# mainBoardV2.net
KiCad netlist of a schematic drawn in EAGLE
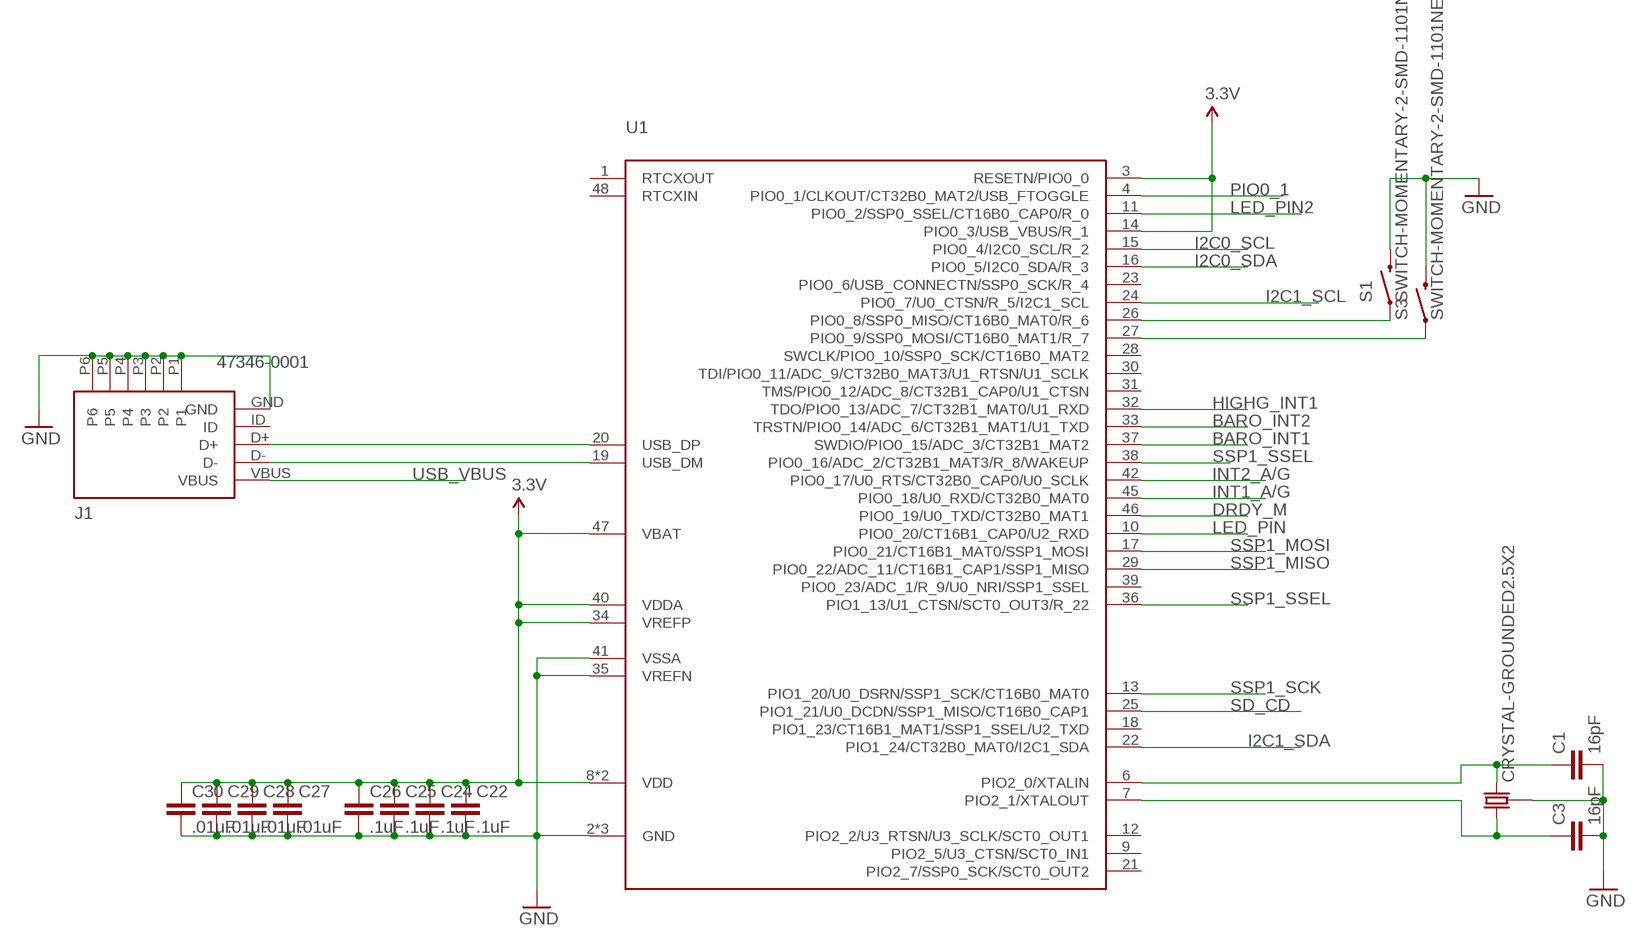
[diagram p0: schematic, sheet 1]
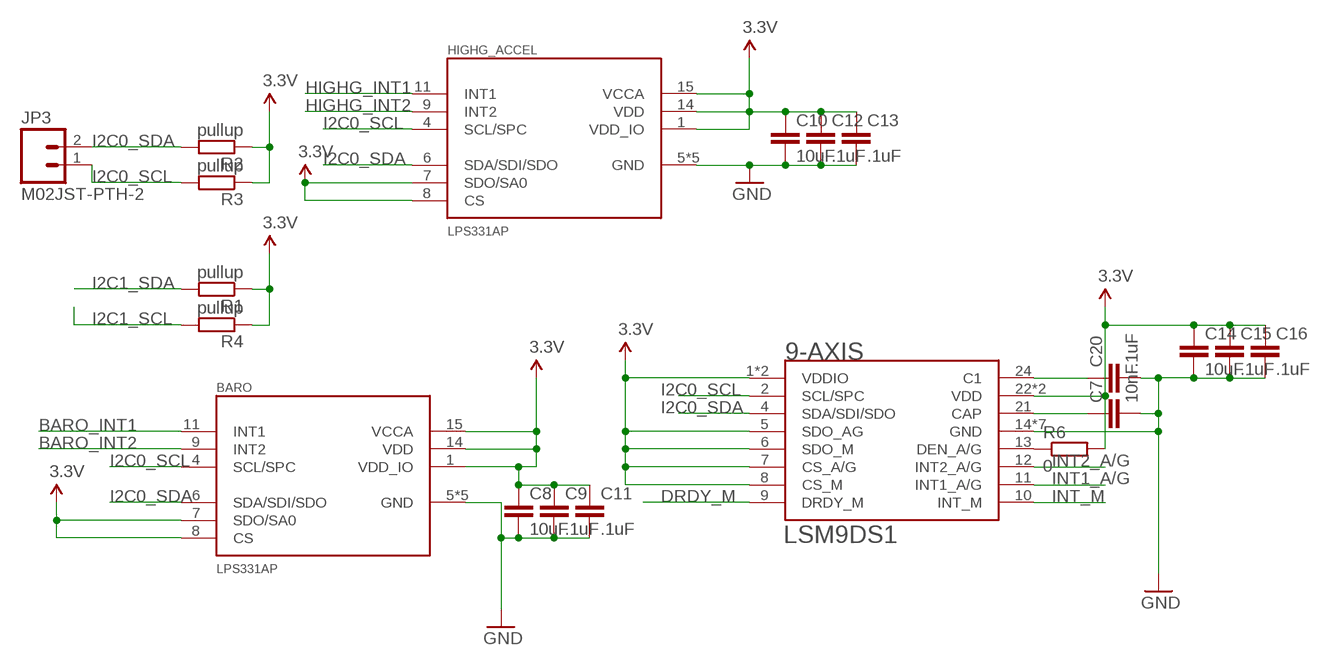
[diagram p1: schematic, sheet 2]
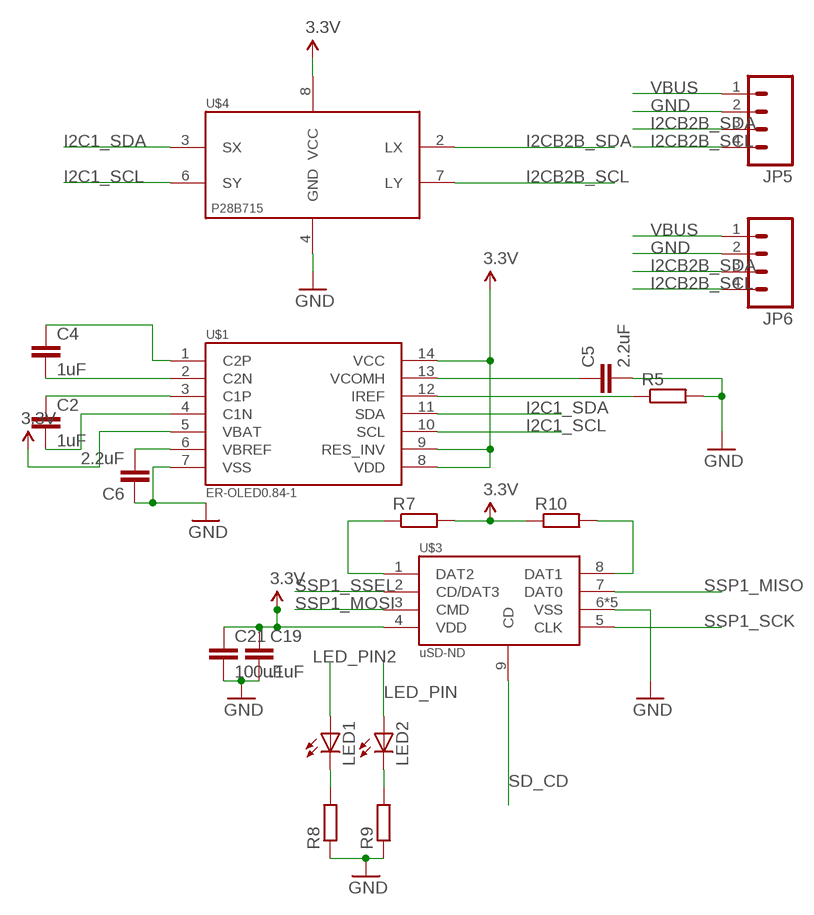
[diagram p2: schematic, sheet 3]
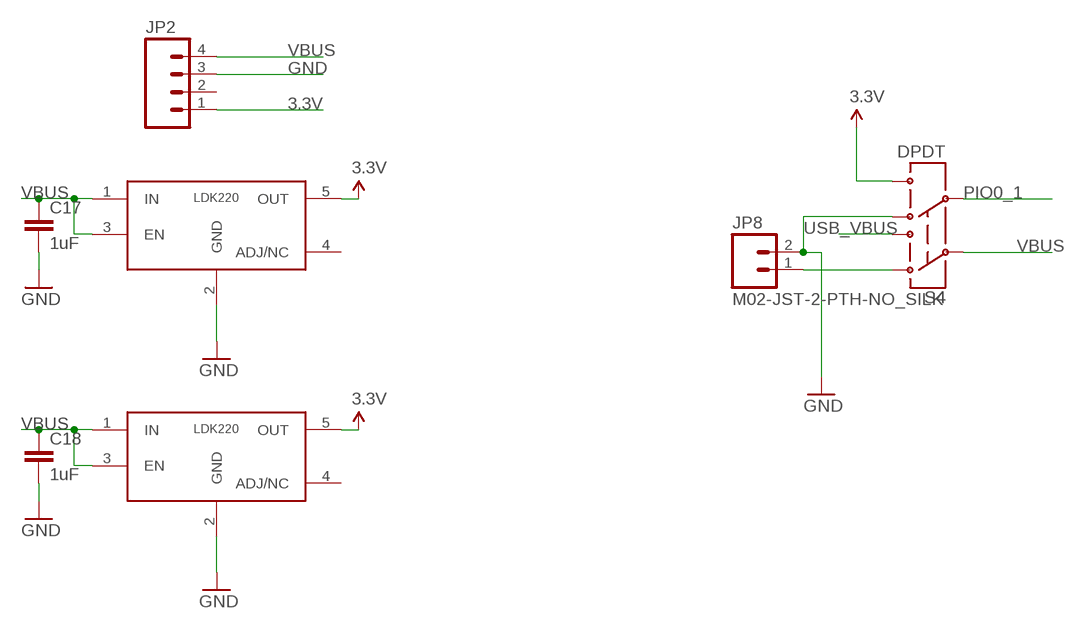
[diagram p3: schematic, sheet 4]

(export (version "E")
  (design (tool "Eeschema 10.0.6"))
  (components
    (comp (ref "C2")
      (value "1uF")
      (footprint "eagle-import:C0402")
      (fields (field (name "MPN") "MC0402X105M6R3CT"))
      (libsource (lib "eagle-import") (part "C0402"))
    )
    (comp (ref "C4")
      (value "1uF")
      (footprint "eagle-import:C0402")
      (fields (field (name "MPN") "MC0402X105M6R3CT"))
      (libsource (lib "eagle-import") (part "C0402"))
    )
    (comp (ref "C5")
      (value "2.2uF")
      (footprint "eagle-import:C0402")
      (fields (field (name "MPN") "C1005X6S0G225M050BC"))
      (libsource (lib "eagle-import") (part "C0402"))
    )
    (comp (ref "C6")
      (value "2.2uF")
      (footprint "eagle-import:C0402")
      (fields (field (name "MPN") "C1005X6S0G225M050BC"))
      (libsource (lib "eagle-import") (part "C0402"))
    )
    (comp (ref "C19")
      (value ".1uF")
      (footprint "eagle-import:C0402")
      (libsource (lib "eagle-import") (part "C0402"))
    )
    (comp (ref "C21")
      (value "100uF")
      (footprint "eagle-import:C1206")
      (libsource (lib "eagle-import") (part "CC1206"))
    )
    (comp (ref "JP5")
      (value "M04JST")
      (footprint "eagle-import:1X04-1.5MM_JST")
      (libsource (lib "eagle-import") (part "M04JST"))
    )
    (comp (ref "JP6")
      (value "M04JST")
      (footprint "eagle-import:1X04-1.5MM_JST")
      (libsource (lib "eagle-import") (part "M04JST"))
    )
    (comp (ref "LED1")
      (value "LEDCHIPLED_0603")
      (footprint "eagle-import:CHIPLED_0603")
      (libsource (lib "eagle-import") (part "LEDCHIPLED_0603"))
    )
    (comp (ref "LED2")
      (value "LEDCHIPLED_0603")
      (footprint "eagle-import:CHIPLED_0603")
      (libsource (lib "eagle-import") (part "LEDCHIPLED_0603"))
    )
    (comp (ref "R5")
      (value "R0402")
      (footprint "eagle-import:R0402")
      (libsource (lib "eagle-import") (part "R0402"))
    )
    (comp (ref "R7")
      (value "R0402")
      (footprint "eagle-import:R0402")
      (libsource (lib "eagle-import") (part "R0402"))
    )
    (comp (ref "R8")
      (value "R0402")
      (footprint "eagle-import:R0402")
      (libsource (lib "eagle-import") (part "R0402"))
    )
    (comp (ref "R9")
      (value "R0402")
      (footprint "eagle-import:R0402")
      (libsource (lib "eagle-import") (part "R0402"))
    )
    (comp (ref "R10")
      (value "R0402")
      (footprint "eagle-import:R0402")
      (libsource (lib "eagle-import") (part "R0402"))
    )
    (comp (ref "U$1")
      (value "ER-OLED0.84-1")
      (footprint "eagle-import:MOLEX_52892-1433")
      (libsource (lib "eagle-import") (part "ER-OLED0.84-1"))
    )
    (comp (ref "U$3")
      (value "MICROSD-CD")
      (footprint "eagle-import:MOLEX_SD-47352-101")
      (libsource (lib "eagle-import") (part "MICROSD-CD"))
    )
    (comp (ref "U$4")
      (value "P82B715")
      (footprint "eagle-import:SO8")
      (libsource (lib "eagle-import") (part "P82B715"))
    )
    (comp (ref "9-AXIS")
      (value "LSM9DS1")
      (footprint "eagle-import:LGA-24L-3.5X3X1")
      (libsource (lib "eagle-import") (part "LSM9DS1"))
    )
    (comp (ref "BARO")
      (value "LPS331AP")
      (footprint "eagle-import:LGA-16-3X3X1")
      (fields (field (name "MPN") "LPS331APTR"))
      (libsource (lib "eagle-import") (part "LPS331AP"))
    )
    (comp (ref "C7")
      (value "10nF")
      (footprint "eagle-import:C0402")
      (fields (field (name "MPN") "S103M47Z5UN63L0R"))
      (libsource (lib "eagle-import") (part "C0402"))
    )
    (comp (ref "C8")
      (value "10uF")
      (footprint "eagle-import:C0402")
      (libsource (lib "eagle-import") (part "C0402"))
    )
    (comp (ref "C9")
      (value ".1uF")
      (footprint "eagle-import:C0402")
      (libsource (lib "eagle-import") (part "C0402"))
    )
    (comp (ref "C10")
      (value "10uF")
      (footprint "eagle-import:C0402")
      (libsource (lib "eagle-import") (part "C0402"))
    )
    (comp (ref "C11")
      (value ".1uF")
      (footprint "eagle-import:C0402")
      (libsource (lib "eagle-import") (part "C0402"))
    )
    (comp (ref "C12")
      (value ".1uF")
      (footprint "eagle-import:C0402")
      (libsource (lib "eagle-import") (part "C0402"))
    )
    (comp (ref "C13")
      (value ".1uF")
      (footprint "eagle-import:C0402")
      (libsource (lib "eagle-import") (part "C0402"))
    )
    (comp (ref "C14")
      (value "10uF")
      (footprint "eagle-import:C0402")
      (libsource (lib "eagle-import") (part "C0402"))
    )
    (comp (ref "C15")
      (value ".1uF")
      (footprint "eagle-import:C0402")
      (libsource (lib "eagle-import") (part "C0402"))
    )
    (comp (ref "C16")
      (value ".1uF")
      (footprint "eagle-import:C0402")
      (libsource (lib "eagle-import") (part "C0402"))
    )
    (comp (ref "C20")
      (value ".1uF")
      (footprint "eagle-import:C0402")
      (fields (field (name "MPN") "S103M47Z5UN63L0R"))
      (libsource (lib "eagle-import") (part "C0402"))
    )
    (comp (ref "HIGHG_ACCEL")
      (value "LPS331AP")
      (footprint "eagle-import:LGA-16-3X3X1")
      (fields (field (name "MPN") "LPS331APTR"))
      (libsource (lib "eagle-import") (part "LPS331AP"))
    )
    (comp (ref "JP3")
      (value "M02JST-PTH-2")
      (footprint "eagle-import:JST-2-PTH")
      (libsource (lib "eagle-import") (part "M02JST-PTH-2"))
    )
    (comp (ref "R1")
      (value "pullup")
      (footprint "eagle-import:R0805")
      (libsource (lib "eagle-import") (part "R0805"))
    )
    (comp (ref "R2")
      (value "pullup")
      (footprint "eagle-import:R0402")
      (libsource (lib "eagle-import") (part "R0402"))
    )
    (comp (ref "R3")
      (value "pullup")
      (footprint "eagle-import:R0402")
      (libsource (lib "eagle-import") (part "R0402"))
    )
    (comp (ref "R4")
      (value "pullup")
      (footprint "eagle-import:R0805")
      (libsource (lib "eagle-import") (part "R0805"))
    )
    (comp (ref "R6")
      (value "0")
      (footprint "eagle-import:R0402")
      (libsource (lib "eagle-import") (part "R0402"))
    )
    (comp (ref "C17")
      (value "1uF")
      (footprint "eagle-import:C0402")
      (libsource (lib "eagle-import") (part "C0402"))
    )
    (comp (ref "C18")
      (value "1uF")
      (footprint "eagle-import:C0402")
      (libsource (lib "eagle-import") (part "C0402"))
    )
    (comp (ref "JP2")
      (value "M04JST")
      (footprint "eagle-import:1X04-1.5MM_JST")
      (libsource (lib "eagle-import") (part "M04JST"))
    )
    (comp (ref "JP8")
      (value "M02-JST-2-PTH-NO_SILK")
      (footprint "eagle-import:JST-2-PTH-NS")
      (libsource (lib "eagle-import") (part "M02-JST-2-PTH-NO_SILK"))
    )
    (comp (ref "S4")
      (value "DPDT")
      (footprint "eagle-import:AYZ0202")
      (libsource (lib "eagle-import") (part "SWITCH-DPDTAYZ0202"))
    )
    (comp (ref "U$2")
      (value "LDK220M33R")
      (footprint "eagle-import:SOT23-5")
      (libsource (lib "eagle-import") (part "LDK220M33R"))
    )
    (comp (ref "U$6")
      (value "LDK220M33R")
      (footprint "eagle-import:SOT23-5")
      (libsource (lib "eagle-import") (part "LDK220M33R"))
    )
    (comp (ref "C1")
      (value "16pF")
      (footprint "eagle-import:C0402")
      (libsource (lib "eagle-import") (part "C0402"))
    )
    (comp (ref "C3")
      (value "16pF")
      (footprint "eagle-import:C0402")
      (libsource (lib "eagle-import") (part "C0402"))
    )
    (comp (ref "C22")
      (value ".1uF")
      (footprint "eagle-import:C0402")
      (libsource (lib "eagle-import") (part "C0402"))
    )
    (comp (ref "C24")
      (value ".1uF")
      (footprint "eagle-import:C0402")
      (libsource (lib "eagle-import") (part "C0402"))
    )
    (comp (ref "C25")
      (value ".1uF")
      (footprint "eagle-import:C0402")
      (libsource (lib "eagle-import") (part "C0402"))
    )
    (comp (ref "C26")
      (value ".1uF")
      (footprint "eagle-import:C0402")
      (libsource (lib "eagle-import") (part "C0402"))
    )
    (comp (ref "C27")
      (value ".01uF")
      (footprint "eagle-import:C0402")
      (libsource (lib "eagle-import") (part "C0402"))
    )
    (comp (ref "C28")
      (value ".01uF")
      (footprint "eagle-import:C0402")
      (libsource (lib "eagle-import") (part "C0402"))
    )
    (comp (ref "C29")
      (value ".01uF")
      (footprint "eagle-import:C0402")
      (libsource (lib "eagle-import") (part "C0402"))
    )
    (comp (ref "C30")
      (value ".01uF")
      (footprint "eagle-import:C0402")
      (libsource (lib "eagle-import") (part "C0402"))
    )
    (comp (ref "J1")
      (value "47346-0001")
      (footprint "eagle-import:MICRO_USB")
      (fields (field (name "PARTNO") "AS-ITM-00021"))
      (libsource (lib "eagle-import") (part "MICRO-USB"))
    )
    (comp (ref "S1")
      (value "SWITCH-MOMENTARY-2-SMD-1101NE")
      (footprint "eagle-import:TACTILE-SWITCH-1101NE")
      (libsource (lib "eagle-import") (part "SWITCH-MOMENTARY-2-SMD-1101NE"))
    )
    (comp (ref "S3")
      (value "SWITCH-MOMENTARY-2-SMD-1101NE")
      (footprint "eagle-import:TACTILE-SWITCH-1101NE")
      (libsource (lib "eagle-import") (part "SWITCH-MOMENTARY-2-SMD-1101NE"))
    )
    (comp (ref "U$5")
      (value "CRYSTAL-GROUNDED2.5X2")
      (footprint "eagle-import:CRYSTAL-SMD-2.5X2")
      (libsource (lib "eagle-import") (part "CRYSTAL-GROUNDED2.5X2"))
    )
    (comp (ref "U1")
      (value "LPC11U68JBD48")
      (footprint "eagle-import:LQFP48")
      (libsource (lib "eagle-import") (part "LPC11U68JBD48"))
    )
  )
  (nets
    (net (code "1") (name "3.3V") (class "Default")
      (node (ref "9-AXIS") (pin "1") (pinfunction "VDDIO_1") (pintype "bidirectional"))
      (node (ref "9-AXIS") (pin "22") (pinfunction "VDD_22") (pintype "bidirectional"))
      (node (ref "9-AXIS") (pin "23") (pinfunction "VDD_23") (pintype "bidirectional"))
      (node (ref "9-AXIS") (pin "3") (pinfunction "VDDIO_3") (pintype "bidirectional"))
      (node (ref "9-AXIS") (pin "5") (pinfunction "SDO_AG_5") (pintype "bidirectional"))
      (node (ref "9-AXIS") (pin "6") (pinfunction "SDO_M_6") (pintype "bidirectional"))
      (node (ref "9-AXIS") (pin "7") (pinfunction "CS_A/G_7") (pintype "bidirectional"))
      (node (ref "9-AXIS") (pin "8") (pinfunction "CS_M_8") (pintype "bidirectional"))
      (node (ref "BARO") (pin "1") (pinfunction "VDD_IO_1") (pintype "bidirectional"))
      (node (ref "BARO") (pin "14") (pinfunction "VDD_14") (pintype "bidirectional"))
      (node (ref "BARO") (pin "15") (pinfunction "VCCA_15") (pintype "bidirectional"))
      (node (ref "BARO") (pin "7") (pinfunction "SDO/SA0_7") (pintype "bidirectional"))
      (node (ref "BARO") (pin "8") (pinfunction "CS_8") (pintype "bidirectional"))
      (node (ref "C10") (pin "1") (pinfunction "1_1") (pintype "passive"))
      (node (ref "C11") (pin "1") (pinfunction "1_1") (pintype "passive"))
      (node (ref "C12") (pin "1") (pinfunction "1_1") (pintype "passive"))
      (node (ref "C13") (pin "1") (pinfunction "1_1") (pintype "passive"))
      (node (ref "C14") (pin "1") (pinfunction "1_1") (pintype "passive"))
      (node (ref "C15") (pin "1") (pinfunction "1_1") (pintype "passive"))
      (node (ref "C16") (pin "1") (pinfunction "1_1") (pintype "passive"))
      (node (ref "C19") (pin "1") (pinfunction "1_1") (pintype "passive"))
      (node (ref "C21") (pin "1") (pinfunction "1_1") (pintype "passive"))
      (node (ref "C22") (pin "1") (pinfunction "1_1") (pintype "passive"))
      (node (ref "C24") (pin "1") (pinfunction "1_1") (pintype "passive"))
      (node (ref "C25") (pin "1") (pinfunction "1_1") (pintype "passive"))
      (node (ref "C26") (pin "1") (pinfunction "1_1") (pintype "passive"))
      (node (ref "C27") (pin "1") (pinfunction "1_1") (pintype "passive"))
      (node (ref "C28") (pin "1") (pinfunction "1_1") (pintype "passive"))
      (node (ref "C29") (pin "1") (pinfunction "1_1") (pintype "passive"))
      (node (ref "C30") (pin "1") (pinfunction "1_1") (pintype "passive"))
      (node (ref "C8") (pin "1") (pinfunction "1_1") (pintype "passive"))
      (node (ref "C9") (pin "1") (pinfunction "1_1") (pintype "passive"))
      (node (ref "HIGHG_ACCEL") (pin "1") (pinfunction "VDD_IO_1") (pintype "bidirectional"))
      (node (ref "HIGHG_ACCEL") (pin "14") (pinfunction "VDD_14") (pintype "bidirectional"))
      (node (ref "HIGHG_ACCEL") (pin "15") (pinfunction "VCCA_15") (pintype "bidirectional"))
      (node (ref "HIGHG_ACCEL") (pin "7") (pinfunction "SDO/SA0_7") (pintype "bidirectional"))
      (node (ref "HIGHG_ACCEL") (pin "8") (pinfunction "CS_8") (pintype "bidirectional"))
      (node (ref "JP2") (pin "1") (pinfunction "1_1") (pintype "passive"))
      (node (ref "R1") (pin "1") (pinfunction "1_1") (pintype "passive"))
      (node (ref "R10") (pin "1") (pinfunction "1_1") (pintype "passive"))
      (node (ref "R2") (pin "1") (pinfunction "1_1") (pintype "passive"))
      (node (ref "R3") (pin "1") (pinfunction "1_1") (pintype "passive"))
      (node (ref "R4") (pin "1") (pinfunction "1_1") (pintype "passive"))
      (node (ref "R6") (pin "2") (pinfunction "2_2") (pintype "passive"))
      (node (ref "R7") (pin "2") (pinfunction "2_2") (pintype "passive"))
      (node (ref "S4") (pin "6") (pinfunction "6_6") (pintype "bidirectional"))
      (node (ref "U$1") (pin "14") (pinfunction "VCC_14") (pintype "bidirectional"))
      (node (ref "U$1") (pin "5") (pinfunction "VBAT_5") (pintype "bidirectional"))
      (node (ref "U$1") (pin "8") (pinfunction "VDD_8") (pintype "bidirectional"))
      (node (ref "U$1") (pin "9") (pinfunction "RES_INV_9") (pintype "bidirectional"))
      (node (ref "U$2") (pin "5") (pinfunction "OUT_5") (pintype "bidirectional"))
      (node (ref "U$3") (pin "4") (pinfunction "VDD_4") (pintype "bidirectional"))
      (node (ref "U$4") (pin "8") (pinfunction "VCC_8") (pintype "bidirectional"))
      (node (ref "U$6") (pin "5") (pinfunction "OUT_5") (pintype "bidirectional"))
      (node (ref "U1") (pin "14") (pinfunction "PIO0_3/USB_VBUS/R_1_14") (pintype "bidirectional"))
      (node (ref "U1") (pin "3") (pinfunction "RESETN/PIO0_0_3") (pintype "bidirectional"))
      (node (ref "U1") (pin "34") (pinfunction "VREFP_34") (pintype "bidirectional"))
      (node (ref "U1") (pin "40") (pinfunction "VDDA_40") (pintype "bidirectional"))
      (node (ref "U1") (pin "44") (pinfunction "VDD_44") (pintype "bidirectional"))
      (node (ref "U1") (pin "47") (pinfunction "VBAT_47") (pintype "bidirectional"))
      (node (ref "U1") (pin "8") (pinfunction "VDD_8") (pintype "bidirectional"))
    )
    (net (code "2") (name "BARO_INT1") (class "Default")
      (node (ref "BARO") (pin "11") (pinfunction "INT1_11") (pintype "bidirectional"))
      (node (ref "U1") (pin "37") (pinfunction "SWDIO/PIO0_15/ADC_3/CT32B1_MAT2_37") (pintype "bidirectional"))
    )
    (net (code "3") (name "BARO_INT2") (class "Default")
      (node (ref "BARO") (pin "9") (pinfunction "INT2_9") (pintype "bidirectional"))
      (node (ref "U1") (pin "33") (pinfunction "TRSTN/PIO0_14/ADC_6/CT32B1_MAT1/U1_TXD_33") (pintype "bidirectional"))
    )
    (net (code "4") (name "DRDY_M") (class "Default")
      (node (ref "9-AXIS") (pin "9") (pinfunction "DRDY_M_9") (pintype "bidirectional"))
      (node (ref "U1") (pin "46") (pinfunction "PIO0_19/U0_TXD/CT32B0_MAT1_46") (pintype "bidirectional"))
    )
    (net (code "5") (name "GND") (class "Default")
      (node (ref "9-AXIS") (pin "14") (pinfunction "GND_14") (pintype "bidirectional"))
      (node (ref "9-AXIS") (pin "15") (pinfunction "GND_15") (pintype "bidirectional"))
      (node (ref "9-AXIS") (pin "16") (pinfunction "GND_16") (pintype "bidirectional"))
      (node (ref "9-AXIS") (pin "17") (pinfunction "GND_17") (pintype "bidirectional"))
      (node (ref "9-AXIS") (pin "18") (pinfunction "GND_18") (pintype "bidirectional"))
      (node (ref "9-AXIS") (pin "19") (pinfunction "GND_19") (pintype "bidirectional"))
      (node (ref "9-AXIS") (pin "20") (pinfunction "GND_20") (pintype "bidirectional"))
      (node (ref "BARO") (pin "10") (pinfunction "GND_10") (pintype "bidirectional"))
      (node (ref "BARO") (pin "12") (pinfunction "GND_12") (pintype "bidirectional"))
      (node (ref "BARO") (pin "13") (pinfunction "GND_13") (pintype "bidirectional"))
      (node (ref "BARO") (pin "16") (pinfunction "GND_16") (pintype "bidirectional"))
      (node (ref "BARO") (pin "5") (pinfunction "GND_5") (pintype "bidirectional"))
      (node (ref "C1") (pin "2") (pinfunction "2_2") (pintype "passive"))
      (node (ref "C10") (pin "2") (pinfunction "2_2") (pintype "passive"))
      (node (ref "C11") (pin "2") (pinfunction "2_2") (pintype "passive"))
      (node (ref "C12") (pin "2") (pinfunction "2_2") (pintype "passive"))
      (node (ref "C13") (pin "2") (pinfunction "2_2") (pintype "passive"))
      (node (ref "C14") (pin "2") (pinfunction "2_2") (pintype "passive"))
      (node (ref "C15") (pin "2") (pinfunction "2_2") (pintype "passive"))
      (node (ref "C16") (pin "2") (pinfunction "2_2") (pintype "passive"))
      (node (ref "C17") (pin "2") (pinfunction "2_2") (pintype "passive"))
      (node (ref "C18") (pin "2") (pinfunction "2_2") (pintype "passive"))
      (node (ref "C19") (pin "2") (pinfunction "2_2") (pintype "passive"))
      (node (ref "C20") (pin "2") (pinfunction "2_2") (pintype "passive"))
      (node (ref "C21") (pin "2") (pinfunction "2_2") (pintype "passive"))
      (node (ref "C22") (pin "2") (pinfunction "2_2") (pintype "passive"))
      (node (ref "C24") (pin "2") (pinfunction "2_2") (pintype "passive"))
      (node (ref "C25") (pin "2") (pinfunction "2_2") (pintype "passive"))
      (node (ref "C26") (pin "2") (pinfunction "2_2") (pintype "passive"))
      (node (ref "C27") (pin "2") (pinfunction "2_2") (pintype "passive"))
      (node (ref "C28") (pin "2") (pinfunction "2_2") (pintype "passive"))
      (node (ref "C29") (pin "2") (pinfunction "2_2") (pintype "passive"))
      (node (ref "C3") (pin "2") (pinfunction "2_2") (pintype "passive"))
      (node (ref "C30") (pin "2") (pinfunction "2_2") (pintype "passive"))
      (node (ref "C5") (pin "2") (pinfunction "2_2") (pintype "passive"))
      (node (ref "C6") (pin "1") (pinfunction "1_1") (pintype "passive"))
      (node (ref "C7") (pin "2") (pinfunction "2_2") (pintype "passive"))
      (node (ref "C8") (pin "2") (pinfunction "2_2") (pintype "passive"))
      (node (ref "C9") (pin "2") (pinfunction "2_2") (pintype "passive"))
      (node (ref "HIGHG_ACCEL") (pin "10") (pinfunction "GND_10") (pintype "bidirectional"))
      (node (ref "HIGHG_ACCEL") (pin "12") (pinfunction "GND_12") (pintype "bidirectional"))
      (node (ref "HIGHG_ACCEL") (pin "13") (pinfunction "GND_13") (pintype "bidirectional"))
      (node (ref "HIGHG_ACCEL") (pin "16") (pinfunction "GND_16") (pintype "bidirectional"))
      (node (ref "HIGHG_ACCEL") (pin "5") (pinfunction "GND_5") (pintype "bidirectional"))
      (node (ref "J1") (pin "GND") (pinfunction "GND_GND") (pintype "bidirectional"))
      (node (ref "J1") (pin "P1") (pinfunction "P1_P1") (pintype "bidirectional"))
      (node (ref "J1") (pin "P2") (pinfunction "P2_P2") (pintype "bidirectional"))
      (node (ref "J1") (pin "P3") (pinfunction "P3_P3") (pintype "bidirectional"))
      (node (ref "J1") (pin "P4") (pinfunction "P4_P4") (pintype "bidirectional"))
      (node (ref "J1") (pin "P5") (pinfunction "P5_P5") (pintype "bidirectional"))
      (node (ref "J1") (pin "P6") (pinfunction "P6_P6") (pintype "bidirectional"))
      (node (ref "JP2") (pin "3") (pinfunction "3_3") (pintype "passive"))
      (node (ref "JP5") (pin "2") (pinfunction "2_2") (pintype "passive"))
      (node (ref "JP6") (pin "2") (pinfunction "2_2") (pintype "passive"))
      (node (ref "JP8") (pin "2") (pinfunction "2_2") (pintype "passive"))
      (node (ref "R5") (pin "2") (pinfunction "2_2") (pintype "passive"))
      (node (ref "R8") (pin "1") (pinfunction "1_1") (pintype "passive"))
      (node (ref "R9") (pin "1") (pinfunction "1_1") (pintype "passive"))
      (node (ref "S1") (pin "2") (pinfunction "2_2") (pintype "passive"))
      (node (ref "S3") (pin "2") (pinfunction "2_2") (pintype "passive"))
      (node (ref "S4") (pin "4") (pinfunction "4_4") (pintype "bidirectional"))
      (node (ref "U$1") (pin "7") (pinfunction "VSS_7") (pintype "bidirectional"))
      (node (ref "U$2") (pin "2") (pinfunction "GND_2") (pintype "bidirectional"))
      (node (ref "U$3") (pin "6") (pinfunction "VSS_6") (pintype "bidirectional"))
      (node (ref "U$3") (pin "G1") (pinfunction "VSS_G1") (pintype "bidirectional"))
      (node (ref "U$3") (pin "G2") (pinfunction "VSS_G2") (pintype "bidirectional"))
      (node (ref "U$3") (pin "G3") (pinfunction "VSS_G3") (pintype "bidirectional"))
      (node (ref "U$3") (pin "G4") (pinfunction "VSS_G4") (pintype "bidirectional"))
      (node (ref "U$4") (pin "4") (pinfunction "GND_4") (pintype "bidirectional"))
      (node (ref "U$5") (pin "GND1") (pinfunction "3_GND1") (pintype "passive"))
      (node (ref "U$5") (pin "GND2") (pinfunction "3_GND2") (pintype "passive"))
      (node (ref "U$6") (pin "2") (pinfunction "GND_2") (pintype "bidirectional"))
      (node (ref "U1") (pin "2") (pinfunction "GND_2") (pintype "bidirectional"))
      (node (ref "U1") (pin "35") (pinfunction "VREFN_35") (pintype "bidirectional"))
      (node (ref "U1") (pin "41") (pinfunction "VSSA_41") (pintype "bidirectional"))
      (node (ref "U1") (pin "43") (pinfunction "GND_43") (pintype "bidirectional"))
      (node (ref "U1") (pin "5") (pinfunction "GND_5") (pintype "bidirectional"))
    )
    (net (code "6") (name "HIGHG_INT1") (class "Default")
      (node (ref "HIGHG_ACCEL") (pin "11") (pinfunction "INT1_11") (pintype "bidirectional"))
      (node (ref "U1") (pin "32") (pinfunction "TDO/PIO0_13/ADC_7/CT32B1_MAT0/U1_RXD_32") (pintype "bidirectional"))
    )
    (net (code "7") (name "HIGHG_INT2") (class "Default")
      (node (ref "HIGHG_ACCEL") (pin "9") (pinfunction "INT2_9") (pintype "bidirectional"))
      (node (ref "U1") (pin "36") (pinfunction "PIO1_13/U1_CTSN/SCT0_OUT3/R_22_36") (pintype "bidirectional"))
    )
    (net (code "8") (name "I2C0_SCL") (class "Default")
      (node (ref "9-AXIS") (pin "2") (pinfunction "SCL/SPC_2") (pintype "bidirectional"))
      (node (ref "BARO") (pin "4") (pinfunction "SCL/SPC_4") (pintype "bidirectional"))
      (node (ref "HIGHG_ACCEL") (pin "4") (pinfunction "SCL/SPC_4") (pintype "bidirectional"))
      (node (ref "JP3") (pin "1") (pinfunction "1_1") (pintype "passive"))
      (node (ref "R3") (pin "2") (pinfunction "2_2") (pintype "passive"))
      (node (ref "U1") (pin "15") (pinfunction "PIO0_4/I2C0_SCL/R_2_15") (pintype "bidirectional"))
    )
    (net (code "9") (name "I2C0_SDA") (class "Default")
      (node (ref "9-AXIS") (pin "4") (pinfunction "SDA/SDI/SDO_4") (pintype "bidirectional"))
      (node (ref "BARO") (pin "6") (pinfunction "SDA/SDI/SDO_6") (pintype "bidirectional"))
      (node (ref "HIGHG_ACCEL") (pin "6") (pinfunction "SDA/SDI/SDO_6") (pintype "bidirectional"))
      (node (ref "JP3") (pin "2") (pinfunction "2_2") (pintype "passive"))
      (node (ref "R2") (pin "2") (pinfunction "2_2") (pintype "passive"))
      (node (ref "U1") (pin "16") (pinfunction "PIO0_5/I2C0_SDA/R_3_16") (pintype "bidirectional"))
    )
    (net (code "10") (name "I2C1_SCL") (class "Default")
      (node (ref "R4") (pin "2") (pinfunction "2_2") (pintype "passive"))
      (node (ref "U$1") (pin "10") (pinfunction "SCL_10") (pintype "bidirectional"))
      (node (ref "U$4") (pin "6") (pinfunction "SY_6") (pintype "bidirectional"))
      (node (ref "U1") (pin "24") (pinfunction "PIO0_7/U0_CTSN/R_5/I2C1_SCL_24") (pintype "bidirectional"))
    )
    (net (code "11") (name "I2C1_SDA") (class "Default")
      (node (ref "R1") (pin "2") (pinfunction "2_2") (pintype "passive"))
      (node (ref "U$1") (pin "11") (pinfunction "SDA_11") (pintype "bidirectional"))
      (node (ref "U$4") (pin "3") (pinfunction "SX_3") (pintype "bidirectional"))
      (node (ref "U1") (pin "22") (pinfunction "PIO1_24/CT32B0_MAT0/I2C1_SDA_22") (pintype "bidirectional"))
    )
    (net (code "12") (name "I2CB2B_SCL") (class "Default")
      (node (ref "JP5") (pin "4") (pinfunction "4_4") (pintype "passive"))
      (node (ref "JP6") (pin "4") (pinfunction "4_4") (pintype "passive"))
      (node (ref "U$4") (pin "7") (pinfunction "LY_7") (pintype "bidirectional"))
    )
    (net (code "13") (name "I2CB2B_SDA") (class "Default")
      (node (ref "JP5") (pin "3") (pinfunction "3_3") (pintype "passive"))
      (node (ref "JP6") (pin "3") (pinfunction "3_3") (pintype "passive"))
      (node (ref "U$4") (pin "2") (pinfunction "LX_2") (pintype "bidirectional"))
    )
    (net (code "14") (name "INT1_A{slash}G") (class "Default")
      (node (ref "9-AXIS") (pin "11") (pinfunction "INT1_A/G_11") (pintype "bidirectional"))
      (node (ref "U1") (pin "45") (pinfunction "PIO0_18/U0_RXD/CT32B0_MAT0_45") (pintype "bidirectional"))
    )
    (net (code "15") (name "INT2_A{slash}G") (class "Default")
      (node (ref "9-AXIS") (pin "12") (pinfunction "INT2_A/G_12") (pintype "bidirectional"))
      (node (ref "U1") (pin "42") (pinfunction "PIO0_17/U0_RTS/CT32B0_CAP0/U0_SCLK_42") (pintype "bidirectional"))
    )
    (net (code "16") (name "INT_M") (class "Default")
      (node (ref "9-AXIS") (pin "10") (pinfunction "INT_M_10") (pintype "bidirectional"))
    )
    (net (code "17") (name "LED_PIN") (class "Default")
      (node (ref "LED2") (pin "A") (pinfunction "A_A") (pintype "passive"))
      (node (ref "U1") (pin "10") (pinfunction "PIO0_20/CT16B1_CAP0/U2_RXD_10") (pintype "bidirectional"))
    )
    (net (code "18") (name "LED_PIN2") (class "Default")
      (node (ref "LED1") (pin "A") (pinfunction "A_A") (pintype "passive"))
      (node (ref "U1") (pin "11") (pinfunction "PIO0_2/SSP0_SSEL/CT16B0_CAP0/R_0_11") (pintype "bidirectional"))
    )
    (net (code "19") (name "Net-(9-AXIS-C1)") (class "Default")
      (node (ref "9-AXIS") (pin "24") (pinfunction "C1_24") (pintype "bidirectional"))
      (node (ref "C20") (pin "1") (pinfunction "1_1") (pintype "passive"))
    )
    (net (code "20") (name "Net-(9-AXIS-CAP)") (class "Default")
      (node (ref "9-AXIS") (pin "21") (pinfunction "CAP_21") (pintype "bidirectional"))
      (node (ref "C7") (pin "1") (pinfunction "1_1") (pintype "passive"))
    )
    (net (code "21") (name "Net-(9-AXIS-DEN_A{slash}G)") (class "Default")
      (node (ref "9-AXIS") (pin "13") (pinfunction "DEN_A/G_13") (pintype "bidirectional"))
      (node (ref "R6") (pin "1") (pinfunction "1_1") (pintype "passive"))
    )
    (net (code "22") (name "Net-(JP8-Pad1)") (class "Default")
      (node (ref "JP8") (pin "1") (pinfunction "1_1") (pintype "passive"))
      (node (ref "S4") (pin "1") (pinfunction "1_1") (pintype "bidirectional"))
    )
    (net (code "23") (name "Net-(LED1-PadC)") (class "Default")
      (node (ref "LED1") (pin "C") (pinfunction "C_C") (pintype "passive"))
      (node (ref "R8") (pin "2") (pinfunction "2_2") (pintype "passive"))
    )
    (net (code "24") (name "Net-(LED2-PadC)") (class "Default")
      (node (ref "LED2") (pin "C") (pinfunction "C_C") (pintype "passive"))
      (node (ref "R9") (pin "2") (pinfunction "2_2") (pintype "passive"))
    )
    (net (code "25") (name "Net-(U$1-C1N)") (class "Default")
      (node (ref "C2") (pin "2") (pinfunction "2_2") (pintype "passive"))
      (node (ref "U$1") (pin "4") (pinfunction "C1N_4") (pintype "bidirectional"))
    )
    (net (code "26") (name "Net-(U$1-C1P)") (class "Default")
      (node (ref "C2") (pin "1") (pinfunction "1_1") (pintype "passive"))
      (node (ref "U$1") (pin "3") (pinfunction "C1P_3") (pintype "bidirectional"))
    )
    (net (code "27") (name "Net-(U$1-C2N)") (class "Default")
      (node (ref "C4") (pin "2") (pinfunction "2_2") (pintype "passive"))
      (node (ref "U$1") (pin "2") (pinfunction "C2N_2") (pintype "bidirectional"))
    )
    (net (code "28") (name "Net-(U$1-C2P)") (class "Default")
      (node (ref "C4") (pin "1") (pinfunction "1_1") (pintype "passive"))
      (node (ref "U$1") (pin "1") (pinfunction "C2P_1") (pintype "bidirectional"))
    )
    (net (code "29") (name "Net-(U$1-IREF)") (class "Default")
      (node (ref "R5") (pin "1") (pinfunction "1_1") (pintype "passive"))
      (node (ref "U$1") (pin "12") (pinfunction "IREF_12") (pintype "bidirectional"))
    )
    (net (code "30") (name "Net-(U$1-VBREF)") (class "Default")
      (node (ref "C6") (pin "2") (pinfunction "2_2") (pintype "passive"))
      (node (ref "U$1") (pin "6") (pinfunction "VBREF_6") (pintype "bidirectional"))
    )
    (net (code "31") (name "Net-(U$1-VCOMH)") (class "Default")
      (node (ref "C5") (pin "1") (pinfunction "1_1") (pintype "passive"))
      (node (ref "U$1") (pin "13") (pinfunction "VCOMH_13") (pintype "bidirectional"))
    )
    (net (code "32") (name "Net-(U$3-DAT1)") (class "Default")
      (node (ref "R10") (pin "2") (pinfunction "2_2") (pintype "passive"))
      (node (ref "U$3") (pin "8") (pinfunction "DAT1_8") (pintype "bidirectional"))
    )
    (net (code "33") (name "Net-(U$3-DAT2)") (class "Default")
      (node (ref "R7") (pin "1") (pinfunction "1_1") (pintype "passive"))
      (node (ref "U$3") (pin "1") (pinfunction "DAT2_1") (pintype "bidirectional"))
    )
    (net (code "34") (name "Net-(U$5-1)") (class "Default")
      (node (ref "C3") (pin "1") (pinfunction "1_1") (pintype "passive"))
      (node (ref "U$5") (pin "P1") (pinfunction "1_P1") (pintype "passive"))
      (node (ref "U1") (pin "7") (pinfunction "PIO2_1/XTALOUT_7") (pintype "bidirectional"))
    )
    (net (code "35") (name "Net-(U$5-2)") (class "Default")
      (node (ref "C1") (pin "1") (pinfunction "1_1") (pintype "passive"))
      (node (ref "U$5") (pin "P2") (pinfunction "2_P2") (pintype "passive"))
      (node (ref "U1") (pin "6") (pinfunction "PIO2_0/XTALIN_6") (pintype "bidirectional"))
    )
    (net (code "36") (name "Net-(U1-PIO0_8{slash}SSP0_MISO{slash}CT16B0_MAT0{slash}R_6)") (class "Default")
      (node (ref "S1") (pin "1") (pinfunction "1_1") (pintype "passive"))
      (node (ref "U1") (pin "26") (pinfunction "PIO0_8/SSP0_MISO/CT16B0_MAT0/R_6_26") (pintype "bidirectional"))
    )
    (net (code "37") (name "Net-(U1-PIO0_9{slash}SSP0_MOSI{slash}CT16B0_MAT1{slash}R_7)") (class "Default")
      (node (ref "S3") (pin "1") (pinfunction "1_1") (pintype "passive"))
      (node (ref "U1") (pin "27") (pinfunction "PIO0_9/SSP0_MOSI/CT16B0_MAT1/R_7_27") (pintype "bidirectional"))
    )
    (net (code "38") (name "Net-(U1-USB_DM)") (class "Default")
      (node (ref "J1") (pin "D-") (pinfunction "D-_D-") (pintype "bidirectional"))
      (node (ref "U1") (pin "19") (pinfunction "USB_DM_19") (pintype "bidirectional"))
    )
    (net (code "39") (name "Net-(U1-USB_DP)") (class "Default")
      (node (ref "J1") (pin "D+") (pinfunction "D+_D+") (pintype "bidirectional"))
      (node (ref "U1") (pin "20") (pinfunction "USB_DP_20") (pintype "bidirectional"))
    )
    (net (code "40") (name "PIO0_1") (class "Default")
      (node (ref "S4") (pin "5") (pinfunction "5_5") (pintype "bidirectional"))
      (node (ref "U1") (pin "4") (pinfunction "PIO0_1/CLKOUT/CT32B0_MAT2/USB_FTOGGLE_4") (pintype "bidirectional"))
    )
    (net (code "41") (name "SD_CD") (class "Default")
      (node (ref "U$3") (pin "9") (pinfunction "CD_9") (pintype "bidirectional"))
      (node (ref "U1") (pin "25") (pinfunction "PIO1_21/U0_DCDN/SSP1_MISO/CT16B0_CAP1_25") (pintype "bidirectional"))
    )
    (net (code "42") (name "SSP1_MISO") (class "Default")
      (node (ref "U$3") (pin "7") (pinfunction "DAT0_7") (pintype "bidirectional"))
      (node (ref "U1") (pin "29") (pinfunction "PIO0_22/ADC_11/CT16B1_CAP1/SSP1_MISO_29") (pintype "bidirectional"))
    )
    (net (code "43") (name "SSP1_MOSI") (class "Default")
      (node (ref "U$3") (pin "3") (pinfunction "CMD_3") (pintype "bidirectional"))
      (node (ref "U1") (pin "17") (pinfunction "PIO0_21/CT16B1_MAT0/SSP1_MOSI_17") (pintype "bidirectional"))
    )
    (net (code "44") (name "SSP1_SCK") (class "Default")
      (node (ref "U$3") (pin "5") (pinfunction "CLK_5") (pintype "bidirectional"))
      (node (ref "U1") (pin "13") (pinfunction "PIO1_20/U0_DSRN/SSP1_SCK/CT16B0_MAT0_13") (pintype "bidirectional"))
    )
    (net (code "45") (name "SSP1_SSEL") (class "Default")
      (node (ref "U$3") (pin "2") (pinfunction "CD/DAT3_2") (pintype "bidirectional"))
      (node (ref "U1") (pin "38") (pinfunction "PIO0_16/ADC_2/CT32B1_MAT3/R_8/WAKEUP_38") (pintype "bidirectional"))
    )
    (net (code "46") (name "USB_VBUS") (class "Default")
      (node (ref "J1") (pin "VBUS") (pinfunction "VBUS_VBUS") (pintype "bidirectional"))
      (node (ref "S4") (pin "3") (pinfunction "3_3") (pintype "bidirectional"))
    )
    (net (code "47") (name "VBUS") (class "Default")
      (node (ref "C17") (pin "1") (pinfunction "1_1") (pintype "passive"))
      (node (ref "C18") (pin "1") (pinfunction "1_1") (pintype "passive"))
      (node (ref "JP2") (pin "4") (pinfunction "4_4") (pintype "passive"))
      (node (ref "JP5") (pin "1") (pinfunction "1_1") (pintype "passive"))
      (node (ref "JP6") (pin "1") (pinfunction "1_1") (pintype "passive"))
      (node (ref "S4") (pin "2") (pinfunction "2_2") (pintype "bidirectional"))
      (node (ref "U$2") (pin "1") (pinfunction "IN_1") (pintype "bidirectional"))
      (node (ref "U$2") (pin "3") (pinfunction "EN_3") (pintype "bidirectional"))
      (node (ref "U$6") (pin "1") (pinfunction "IN_1") (pintype "bidirectional"))
      (node (ref "U$6") (pin "3") (pinfunction "EN_3") (pintype "bidirectional"))
    )
    (net (code "48") (name "unconnected-(J1-PadID)") (class "Default")
      (node (ref "J1") (pin "ID") (pinfunction "ID_ID") (pintype "bidirectional"))
    )
    (net (code "49") (name "unconnected-(JP2-Pad2)") (class "Default")
      (node (ref "JP2") (pin "2") (pinfunction "2_2") (pintype "passive"))
    )
    (net (code "50") (name "unconnected-(U$2-ADJ{slash}NC-Pad4)") (class "Default")
      (node (ref "U$2") (pin "4") (pinfunction "ADJ/NC_4") (pintype "bidirectional"))
    )
    (net (code "51") (name "unconnected-(U$6-ADJ{slash}NC-Pad4)") (class "Default")
      (node (ref "U$6") (pin "4") (pinfunction "ADJ/NC_4") (pintype "bidirectional"))
    )
    (net (code "52") (name "unconnected-(U1-PIO0_6{slash}USB_CONNECTN{slash}SSP0_SCK{slash}R_4-Pad23)") (class "Default")
      (node (ref "U1") (pin "23") (pinfunction "PIO0_6/USB_CONNECTN/SSP0_SCK/R_4_23") (pintype "bidirectional"))
    )
    (net (code "53") (name "unconnected-(U1-PIO0_23{slash}ADC_1{slash}R_9{slash}U0_NRI{slash}SSP1_SSEL-Pad39)") (class "Default")
      (node (ref "U1") (pin "39") (pinfunction "PIO0_23/ADC_1/R_9/U0_NRI/SSP1_SSEL_39") (pintype "bidirectional"))
    )
    (net (code "54") (name "unconnected-(U1-PIO1_23{slash}CT16B1_MAT1{slash}SSP1_SSEL{slash}U2_TXD-Pad18)") (class "Default")
      (node (ref "U1") (pin "18") (pinfunction "PIO1_23/CT16B1_MAT1/SSP1_SSEL/U2_TXD_18") (pintype "bidirectional"))
    )
    (net (code "55") (name "unconnected-(U1-PIO2_2{slash}U3_RTSN{slash}U3_SCLK{slash}SCT0_OUT1-Pad12)") (class "Default")
      (node (ref "U1") (pin "12") (pinfunction "PIO2_2/U3_RTSN/U3_SCLK/SCT0_OUT1_12") (pintype "bidirectional"))
    )
    (net (code "56") (name "unconnected-(U1-PIO2_5{slash}U3_CTSN{slash}SCT0_IN1-Pad9)") (class "Default")
      (node (ref "U1") (pin "9") (pinfunction "PIO2_5/U3_CTSN/SCT0_IN1_9") (pintype "bidirectional"))
    )
    (net (code "57") (name "unconnected-(U1-PIO2_7{slash}SSP0_SCK{slash}SCT0_OUT2-Pad21)") (class "Default")
      (node (ref "U1") (pin "21") (pinfunction "PIO2_7/SSP0_SCK/SCT0_OUT2_21") (pintype "bidirectional"))
    )
    (net (code "58") (name "unconnected-(U1-RTCXIN-Pad48)") (class "Default")
      (node (ref "U1") (pin "48") (pinfunction "RTCXIN_48") (pintype "bidirectional"))
    )
    (net (code "59") (name "unconnected-(U1-RTCXOUT-Pad1)") (class "Default")
      (node (ref "U1") (pin "1") (pinfunction "RTCXOUT_1") (pintype "bidirectional"))
    )
    (net (code "60") (name "unconnected-(U1-SWCLK{slash}PIO0_10{slash}SSP0_SCK{slash}CT16B0_MAT2-Pad28)") (class "Default")
      (node (ref "U1") (pin "28") (pinfunction "SWCLK/PIO0_10/SSP0_SCK/CT16B0_MAT2_28") (pintype "bidirectional"))
    )
    (net (code "61") (name "unconnected-(U1-TDI{slash}PIO0_11{slash}ADC_9{slash}CT32B0_MAT3{slash}U1_RTSN{slash}U1_SCLK-Pad30)") (class "Default")
      (node (ref "U1") (pin "30") (pinfunction "TDI/PIO0_11/ADC_9/CT32B0_MAT3/U1_RTSN/U1_SCLK_30") (pintype "bidirectional"))
    )
    (net (code "62") (name "unconnected-(U1-TMS{slash}PIO0_12{slash}ADC_8{slash}CT32B1_CAP0{slash}U1_CTSN-Pad31)") (class "Default")
      (node (ref "U1") (pin "31") (pinfunction "TMS/PIO0_12/ADC_8/CT32B1_CAP0/U1_CTSN_31") (pintype "bidirectional"))
    )
  )
)
